# Split_Pumps.net
KiCad netlist of a schematic drawn in Altium Designer
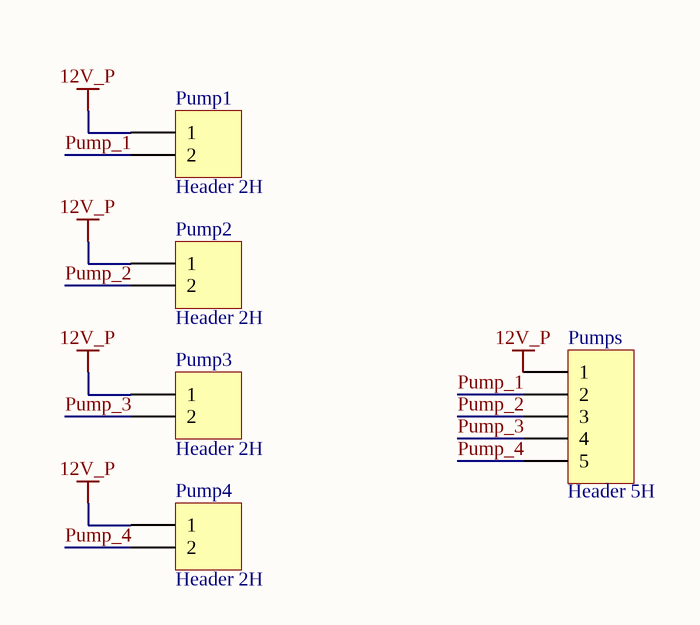
[diagram p0: Split_Pumps.SchDoc]

(export (version "E")
  (design (tool "Eeschema 10.0.6"))
  (components
    (comp (ref "Pump1")
      (value "Header 2H")
      (footprint "S2B-XH-A")
      (description "Header, 2-Pin, Right Angle")
      (fields (field (name "PUBLISHER") "Altium Limited"))
      (libsource (lib "Miscellaneous Connectors") (part "Header 2H"))
    )
    (comp (ref "Pump2")
      (value "Header 2H")
      (footprint "S2B-XH-A")
      (description "Header, 2-Pin, Right Angle")
      (fields (field (name "PUBLISHER") "Altium Limited"))
      (libsource (lib "Miscellaneous Connectors") (part "Header 2H"))
    )
    (comp (ref "Pump3")
      (value "Header 2H")
      (footprint "S2B-XH-A")
      (description "Header, 2-Pin, Right Angle")
      (fields (field (name "PUBLISHER") "Altium Limited"))
      (libsource (lib "Miscellaneous Connectors") (part "Header 2H"))
    )
    (comp (ref "Pump4")
      (value "Header 2H")
      (footprint "S2B-XH-A")
      (description "Header, 2-Pin, Right Angle")
      (fields (field (name "PUBLISHER") "Altium Limited"))
      (libsource (lib "Miscellaneous Connectors") (part "Header 2H"))
    )
    (comp (ref "Pumps")
      (value "Header 5H")
      (footprint "S5B-XH-A")
      (description "Header, 5-Pin, Right Angle")
      (fields (field (name "PUBLISHER") "Altium Limited"))
      (libsource (lib "Miscellaneous Connectors") (part "Header 5H"))
    )
  )
  (nets
    (net (code "1") (name "/Pump_1") (class "Default")
      (node (ref "Pump1") (pin "2") (pinfunction "2_2") (pintype "passive"))
      (node (ref "Pumps") (pin "2") (pinfunction "2_2") (pintype "passive"))
    )
    (net (code "2") (name "/Pump_2") (class "Default")
      (node (ref "Pump2") (pin "2") (pinfunction "2_2") (pintype "passive"))
      (node (ref "Pumps") (pin "3") (pinfunction "3_3") (pintype "passive"))
    )
    (net (code "3") (name "/Pump_3") (class "Default")
      (node (ref "Pump3") (pin "2") (pinfunction "2_2") (pintype "passive"))
      (node (ref "Pumps") (pin "4") (pinfunction "4_4") (pintype "passive"))
    )
    (net (code "4") (name "/Pump_4") (class "Default")
      (node (ref "Pump4") (pin "2") (pinfunction "2_2") (pintype "passive"))
      (node (ref "Pumps") (pin "5") (pinfunction "5_5") (pintype "passive"))
    )
    (net (code "5") (name "12V_P") (class "Default")
      (node (ref "Pump1") (pin "1") (pinfunction "1_1") (pintype "passive"))
      (node (ref "Pump2") (pin "1") (pinfunction "1_1") (pintype "passive"))
      (node (ref "Pump3") (pin "1") (pinfunction "1_1") (pintype "passive"))
      (node (ref "Pump4") (pin "1") (pinfunction "1_1") (pintype "passive"))
      (node (ref "Pumps") (pin "1") (pinfunction "1_1") (pintype "passive"))
    )
  )
)
